# ST-Link_V2.net
KiCad netlist of a schematic drawn in Altium Designer
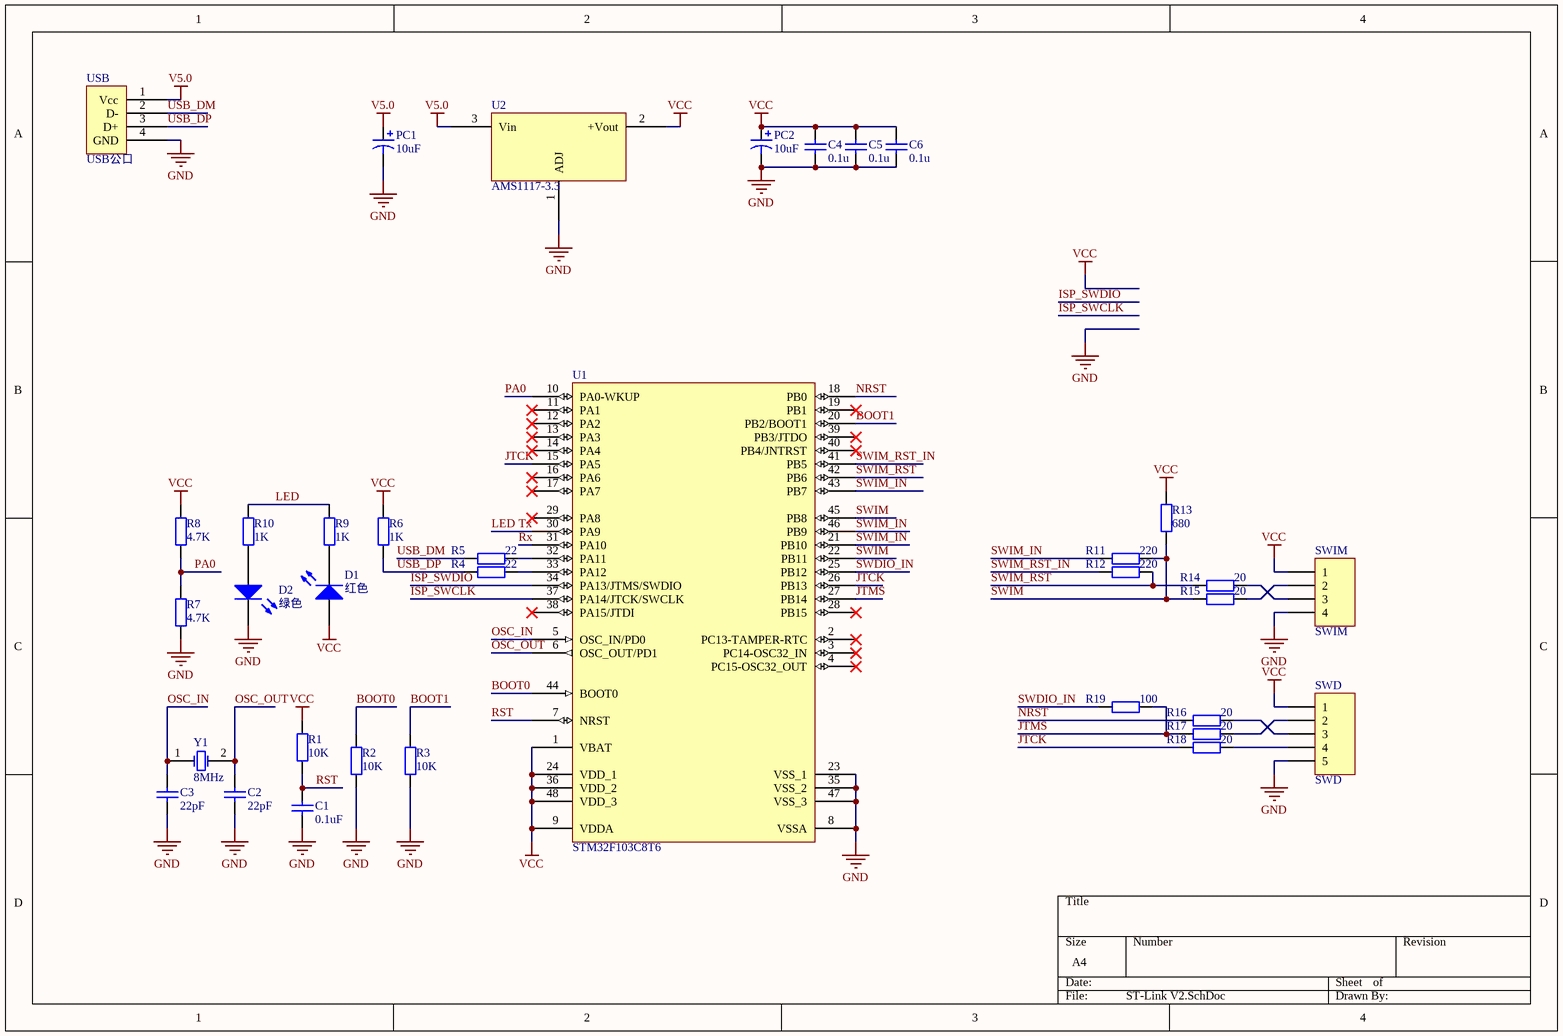
[diagram p0: ST-Link V2.SchDoc]

(export (version "E")
  (design (tool "Eeschema 10.0.6"))
  (components
    (comp (ref "C1")
      (value "0.1uF")
      (footprint "Teacher:C0603")
      (description "Capacitor")
      (fields (field (name "PUBLISHER") "Altium Limited"))
      (libsource (lib "Miscellaneous Devices") (part "Cap"))
    )
    (comp (ref "C2")
      (value "22pF")
      (footprint "Teacher:C0603")
      (description "Capacitor")
      (fields (field (name "PUBLISHER") "Altium Limited"))
      (libsource (lib "Miscellaneous Devices") (part "Cap"))
    )
    (comp (ref "C3")
      (value "22pF")
      (footprint "Teacher:C0603")
      (description "Capacitor")
      (fields (field (name "PUBLISHER") "Altium Limited"))
      (libsource (lib "Miscellaneous Devices") (part "Cap"))
    )
    (comp (ref "C4")
      (value "0.1u")
      (description "Capacitor")
      (fields (field (name "PUBLISHER") "Altium Limited"))
      (libsource (lib "Miscellaneous Devices") (part "Cap"))
    )
    (comp (ref "C5")
      (value "0.1u")
      (description "Capacitor")
      (fields (field (name "PUBLISHER") "Altium Limited"))
      (libsource (lib "Miscellaneous Devices") (part "Cap"))
    )
    (comp (ref "C6")
      (value "0.1u")
      (description "Capacitor")
      (fields (field (name "PUBLISHER") "Altium Limited"))
      (libsource (lib "Miscellaneous Devices") (part "Cap"))
    )
    (comp (ref "D1")
      (value "红色")
      (footprint "ADqun:LED0603")
      (description "Typical RED, GREEN, YELLOW, AMBER GaAs LED")
      (fields (field (name "PUBLISHER") "Altium Limited"))
      (libsource (lib "Miscellaneous Devices") (part "LED2"))
    )
    (comp (ref "D2")
      (value "绿色")
      (footprint "ADqun:LED0603")
      (description "Typical RED, GREEN, YELLOW, AMBER GaAs LED")
      (fields (field (name "PUBLISHER") "Altium Limited"))
      (libsource (lib "Miscellaneous Devices") (part "LED2"))
    )
    (comp (ref "PC1")
      (value "10uF")
      (footprint "Teacher:C1206A")
      (description "Polarized Capacitor (Surface Mount)")
      (fields (field (name "PUBLISHER") "Altium Limited"))
      (libsource (lib "Miscellaneous Devices") (part "Cap Pol3"))
    )
    (comp (ref "PC2")
      (value "10uF")
      (footprint "Teacher:C1206A")
      (description "Polarized Capacitor (Surface Mount)")
      (fields (field (name "PUBLISHER") "Altium Limited"))
      (libsource (lib "Miscellaneous Devices") (part "Cap Pol3"))
    )
    (comp (ref "R1")
      (value "10K")
      (footprint "Teacher:R0603")
      (description "Resistor")
      (fields (field (name "PUBLISHER") "Altium Limited"))
      (libsource (lib "") (part "Res2_2"))
    )
    (comp (ref "R2")
      (value "10K")
      (footprint "Teacher:R0603")
      (description "Resistor")
      (fields (field (name "PUBLISHER") "Altium Limited"))
      (libsource (lib "") (part "Res2_2"))
    )
    (comp (ref "R3")
      (value "10K")
      (footprint "Teacher:R0603")
      (description "Resistor")
      (fields (field (name "PUBLISHER") "Altium Limited"))
      (libsource (lib "") (part "Res2_2"))
    )
    (comp (ref "R4")
      (value "22")
      (footprint "Teacher:R0603")
      (description "Resistor")
      (fields (field (name "PUBLISHER") "Altium Limited"))
      (libsource (lib "") (part "Res2_1"))
    )
    (comp (ref "R5")
      (value "22")
      (footprint "Teacher:R0603")
      (description "Resistor")
      (fields (field (name "PUBLISHER") "Altium Limited"))
      (libsource (lib "") (part "Res2_1"))
    )
    (comp (ref "R6")
      (value "1K")
      (footprint "Teacher:R0603")
      (description "Resistor")
      (fields (field (name "PUBLISHER") "Altium Limited"))
      (libsource (lib "") (part "Res2_3"))
    )
    (comp (ref "R7")
      (value "4.7K")
      (footprint "Teacher:R0603")
      (description "Resistor")
      (fields (field (name "PUBLISHER") "Altium Limited"))
      (libsource (lib "") (part "Res2_3"))
    )
    (comp (ref "R8")
      (value "4.7K")
      (footprint "Teacher:R0603")
      (description "Resistor")
      (fields (field (name "PUBLISHER") "Altium Limited"))
      (libsource (lib "") (part "Res2_3"))
    )
    (comp (ref "R9")
      (value "1K")
      (footprint "Teacher:R0603")
      (description "Resistor")
      (fields (field (name "PUBLISHER") "Altium Limited"))
      (libsource (lib "") (part "Res2_3"))
    )
    (comp (ref "R10")
      (value "1K")
      (footprint "Teacher:R0603")
      (description "Resistor")
      (fields (field (name "PUBLISHER") "Altium Limited"))
      (libsource (lib "") (part "Res2_3"))
    )
    (comp (ref "R11")
      (value "220")
      (footprint "Teacher:R0603")
      (description "Resistor")
      (fields (field (name "PUBLISHER") "Altium Limited"))
      (libsource (lib "Miscellaneous Devices") (part "Res2"))
    )
    (comp (ref "R12")
      (value "220")
      (footprint "Teacher:R0603")
      (description "Resistor")
      (fields (field (name "PUBLISHER") "Altium Limited"))
      (libsource (lib "Miscellaneous Devices") (part "Res2"))
    )
    (comp (ref "R13")
      (value "680")
      (footprint "Teacher:R0603")
      (description "Resistor")
      (fields (field (name "PUBLISHER") "Altium Limited"))
      (libsource (lib "") (part "Res2_2"))
    )
    (comp (ref "R14")
      (value "20")
      (footprint "Teacher:R0603")
      (description "Resistor")
      (fields (field (name "PUBLISHER") "Altium Limited"))
      (libsource (lib "") (part "Res2_1"))
    )
    (comp (ref "R15")
      (value "20")
      (footprint "Teacher:R0603")
      (description "Resistor")
      (fields (field (name "PUBLISHER") "Altium Limited"))
      (libsource (lib "") (part "Res2_1"))
    )
    (comp (ref "R16")
      (value "20")
      (footprint "Teacher:R0603")
      (description "Resistor")
      (fields (field (name "PUBLISHER") "Altium Limited"))
      (libsource (lib "") (part "Res2_1"))
    )
    (comp (ref "R17")
      (value "20")
      (footprint "Teacher:R0603")
      (description "Resistor")
      (fields (field (name "PUBLISHER") "Altium Limited"))
      (libsource (lib "") (part "Res2_1"))
    )
    (comp (ref "R18")
      (value "20")
      (footprint "Teacher:R0603")
      (description "Resistor")
      (fields (field (name "PUBLISHER") "Altium Limited"))
      (libsource (lib "") (part "Res2_1"))
    )
    (comp (ref "R19")
      (value "100")
      (footprint "Teacher:R0603")
      (description "Resistor")
      (fields (field (name "PUBLISHER") "Altium Limited"))
      (libsource (lib "") (part "Res2_1"))
    )
    (comp (ref "SWD")
      (value "SWD")
      (footprint "HDR1X5")
      (description "Header, 5-Pin")
      (fields (field (name "PUBLISHER") "Altium Limited"))
      (libsource (lib "Miscellaneous Connectors") (part "Header 5"))
    )
    (comp (ref "SWIM")
      (value "SWIM")
      (footprint "HDR1X4")
      (description "Header, 4-Pin")
      (fields (field (name "PUBLISHER") "Altium Limited"))
      (libsource (lib "Miscellaneous Connectors") (part "Header 4"))
    )
    (comp (ref "U1")
      (value "STM32F103C8T6")
      (footprint "LQFP48_M")
      (description "STM32 ARM-based 32-bit MCU with 64 Kbytes Flash, 48-pin LQFP, Industrial Temperature")
      (fields (field (name "PUBLISHER") "Altium Limited"))
      (libsource (lib "ST Microcontroller 32-Bit STM32") (part "STM32F103C8T6"))
    )
    (comp (ref "U2")
      (value "AMS1117-3.3")
      (footprint "Teacher:SOT-223")
      (libsource (lib "Protel DOS Schematic Libraries") (part "LM117T"))
    )
    (comp (ref "USB") (value "USB公口") (footprint "USB-H") (libsource (lib "USB公口") (part "USB公口")))
    (comp (ref "Y1")
      (value "8MHz")
      (footprint "paul_pcb:JZ")
      (description "Crystal Oscillator")
      (fields (field (name "PUBLISHER") "Altium Limited"))
      (libsource (lib "Miscellaneous Devices") (part "XTAL"))
    )
  )
  (nets
    (net (code "1") (name "/BOOT0") (class "Default")
      (node (ref "R2") (pin "2") (pinfunction "2_2") (pintype "passive"))
      (node (ref "U1") (pin "44") (pinfunction "BOOT0_44") (pintype "input"))
    )
    (net (code "2") (name "/BOOT1") (class "Default")
      (node (ref "R3") (pin "2") (pinfunction "2_2") (pintype "passive"))
      (node (ref "U1") (pin "20") (pinfunction "PB2/BOOT1_20") (pintype "bidirectional"))
    )
    (net (code "3") (name "/ISP_SWCLK") (class "Default")
      (node (ref "U1") (pin "37") (pinfunction "PA14/JTCK/SWCLK_37") (pintype "bidirectional"))
    )
    (net (code "4") (name "/ISP_SWDIO") (class "Default")
      (node (ref "U1") (pin "34") (pinfunction "PA13/JTMS/SWDIO_34") (pintype "bidirectional"))
    )
    (net (code "5") (name "/JTCK") (class "Default")
      (node (ref "R18") (pin "2") (pinfunction "2_2") (pintype "passive"))
      (node (ref "U1") (pin "15") (pinfunction "PA5_15") (pintype "bidirectional"))
      (node (ref "U1") (pin "26") (pinfunction "PB13_26") (pintype "bidirectional"))
    )
    (net (code "6") (name "/JTMS") (class "Default")
      (node (ref "R17") (pin "2") (pinfunction "2_2") (pintype "passive"))
      (node (ref "R19") (pin "1") (pinfunction "1_1") (pintype "passive"))
      (node (ref "U1") (pin "27") (pinfunction "PB14_27") (pintype "bidirectional"))
    )
    (net (code "7") (name "/LED") (class "Default")
      (node (ref "R10") (pin "1") (pinfunction "1_1") (pintype "passive"))
      (node (ref "R9") (pin "1") (pinfunction "1_1") (pintype "passive"))
      (node (ref "U1") (pin "30") (pinfunction "PA9_30") (pintype "bidirectional"))
    )
    (net (code "8") (name "/NRST") (class "Default")
      (node (ref "R16") (pin "2") (pinfunction "2_2") (pintype "passive"))
      (node (ref "U1") (pin "18") (pinfunction "PB0_18") (pintype "bidirectional"))
    )
    (net (code "9") (name "/OSC_IN") (class "Default")
      (node (ref "C3") (pin "1") (pinfunction "1_1") (pintype "passive"))
      (node (ref "U1") (pin "5") (pinfunction "OSC_IN/PD0_5") (pintype "input"))
      (node (ref "Y1") (pin "1") (pinfunction "OSC1_1") (pintype "passive"))
    )
    (net (code "10") (name "/OSC_OUT") (class "Default")
      (node (ref "C2") (pin "1") (pinfunction "1_1") (pintype "passive"))
      (node (ref "U1") (pin "6") (pinfunction "OSC_OUT/PD1_6") (pintype "output"))
      (node (ref "Y1") (pin "2") (pinfunction "OSC2_2") (pintype "passive"))
    )
    (net (code "11") (name "/PA0") (class "Default")
      (node (ref "R7") (pin "1") (pinfunction "1_1") (pintype "passive"))
      (node (ref "R8") (pin "2") (pinfunction "2_2") (pintype "passive"))
      (node (ref "U1") (pin "10") (pinfunction "PA0-WKUP_10") (pintype "bidirectional"))
    )
    (net (code "12") (name "/RST") (class "Default")
      (node (ref "C1") (pin "1") (pinfunction "1_1") (pintype "passive"))
      (node (ref "R1") (pin "1") (pinfunction "1_1") (pintype "passive"))
      (node (ref "U1") (pin "7") (pinfunction "NRST_7") (pintype "bidirectional"))
    )
    (net (code "13") (name "/Rx") (class "Default")
      (node (ref "U1") (pin "31") (pinfunction "PA10_31") (pintype "bidirectional"))
    )
    (net (code "14") (name "/SWDIO_IN") (class "Default")
      (node (ref "R19") (pin "2") (pinfunction "2_2") (pintype "passive"))
      (node (ref "U1") (pin "25") (pinfunction "PB12_25") (pintype "bidirectional"))
    )
    (net (code "15") (name "/SWIM") (class "Default")
      (node (ref "R11") (pin "2") (pinfunction "2_2") (pintype "passive"))
      (node (ref "R13") (pin "1") (pinfunction "1_1") (pintype "passive"))
      (node (ref "R15") (pin "2") (pinfunction "2_2") (pintype "passive"))
      (node (ref "U1") (pin "22") (pinfunction "PB11_22") (pintype "bidirectional"))
      (node (ref "U1") (pin "45") (pinfunction "PB8_45") (pintype "bidirectional"))
    )
    (net (code "16") (name "/SWIM_IN") (class "Default")
      (node (ref "R11") (pin "1") (pinfunction "1_1") (pintype "passive"))
      (node (ref "U1") (pin "21") (pinfunction "PB10_21") (pintype "bidirectional"))
      (node (ref "U1") (pin "43") (pinfunction "PB7_43") (pintype "bidirectional"))
      (node (ref "U1") (pin "46") (pinfunction "PB9_46") (pintype "bidirectional"))
    )
    (net (code "17") (name "/SWIM_RST") (class "Default")
      (node (ref "R12") (pin "2") (pinfunction "2_2") (pintype "passive"))
      (node (ref "R14") (pin "2") (pinfunction "2_2") (pintype "passive"))
      (node (ref "U1") (pin "42") (pinfunction "PB6_42") (pintype "bidirectional"))
    )
    (net (code "18") (name "/SWIM_RST_IN") (class "Default")
      (node (ref "R12") (pin "1") (pinfunction "1_1") (pintype "passive"))
      (node (ref "U1") (pin "41") (pinfunction "PB5_41") (pintype "bidirectional"))
    )
    (net (code "19") (name "/USB_DM") (class "Default")
      (node (ref "R5") (pin "2") (pinfunction "2_2") (pintype "passive"))
      (node (ref "USB") (pin "2") (pinfunction "D-_2") (pintype "passive"))
    )
    (net (code "20") (name "/USB_DP") (class "Default")
      (node (ref "R4") (pin "2") (pinfunction "2_2") (pintype "passive"))
      (node (ref "R6") (pin "2") (pinfunction "2_2") (pintype "passive"))
      (node (ref "USB") (pin "3") (pinfunction "D+_3") (pintype "passive"))
    )
    (net (code "21") (name "GND") (class "Default")
      (node (ref "C1") (pin "2") (pinfunction "2_2") (pintype "passive"))
      (node (ref "C2") (pin "2") (pinfunction "2_2") (pintype "passive"))
      (node (ref "C3") (pin "2") (pinfunction "2_2") (pintype "passive"))
      (node (ref "C4") (pin "2") (pinfunction "2_2") (pintype "passive"))
      (node (ref "C5") (pin "2") (pinfunction "2_2") (pintype "passive"))
      (node (ref "C6") (pin "2") (pinfunction "2_2") (pintype "passive"))
      (node (ref "D2") (pin "2") (pinfunction "K_2") (pintype "passive"))
      (node (ref "PC1") (pin "2") (pinfunction "2_2") (pintype "passive"))
      (node (ref "PC2") (pin "2") (pinfunction "2_2") (pintype "passive"))
      (node (ref "R2") (pin "1") (pinfunction "1_1") (pintype "passive"))
      (node (ref "R3") (pin "1") (pinfunction "1_1") (pintype "passive"))
      (node (ref "R7") (pin "2") (pinfunction "2_2") (pintype "passive"))
      (node (ref "SWD") (pin "5") (pinfunction "5_5") (pintype "passive"))
      (node (ref "SWIM") (pin "4") (pinfunction "4_4") (pintype "passive"))
      (node (ref "U1") (pin "23") (pinfunction "VSS_1_23") (pintype "power_in"))
      (node (ref "U1") (pin "35") (pinfunction "VSS_2_35") (pintype "power_in"))
      (node (ref "U1") (pin "47") (pinfunction "VSS_3_47") (pintype "power_in"))
      (node (ref "U1") (pin "8") (pinfunction "VSSA_8") (pintype "power_in"))
      (node (ref "U2") (pin "1") (pinfunction "ADJ_1") (pintype "passive"))
      (node (ref "USB") (pin "4") (pinfunction "GND_4") (pintype "passive"))
    )
    (net (code "22") (name "Net-(D1-K)") (class "Default")
      (node (ref "D1") (pin "2") (pinfunction "K_2") (pintype "passive"))
      (node (ref "R9") (pin "2") (pinfunction "2_2") (pintype "passive"))
    )
    (net (code "23") (name "Net-(D2-A)") (class "Default")
      (node (ref "D2") (pin "1") (pinfunction "A_1") (pintype "passive"))
      (node (ref "R10") (pin "2") (pinfunction "2_2") (pintype "passive"))
    )
    (net (code "24") (name "Net-(R14-Pad1)") (class "Default")
      (node (ref "R14") (pin "1") (pinfunction "1_1") (pintype "passive"))
      (node (ref "SWIM") (pin "3") (pinfunction "3_3") (pintype "passive"))
    )
    (net (code "25") (name "Net-(R15-Pad1)") (class "Default")
      (node (ref "R15") (pin "1") (pinfunction "1_1") (pintype "passive"))
      (node (ref "SWIM") (pin "2") (pinfunction "2_2") (pintype "passive"))
    )
    (net (code "26") (name "Net-(R16-Pad1)") (class "Default")
      (node (ref "R16") (pin "1") (pinfunction "1_1") (pintype "passive"))
      (node (ref "SWD") (pin "3") (pinfunction "3_3") (pintype "passive"))
    )
    (net (code "27") (name "Net-(R17-Pad1)") (class "Default")
      (node (ref "R17") (pin "1") (pinfunction "1_1") (pintype "passive"))
      (node (ref "SWD") (pin "2") (pinfunction "2_2") (pintype "passive"))
    )
    (net (code "28") (name "Net-(R18-Pad1)") (class "Default")
      (node (ref "R18") (pin "1") (pinfunction "1_1") (pintype "passive"))
      (node (ref "SWD") (pin "4") (pinfunction "4_4") (pintype "passive"))
    )
    (net (code "29") (name "Net-(U1-PA11)") (class "Default")
      (node (ref "R5") (pin "1") (pinfunction "1_1") (pintype "passive"))
      (node (ref "U1") (pin "32") (pinfunction "PA11_32") (pintype "bidirectional"))
    )
    (net (code "30") (name "Net-(U1-PA12)") (class "Default")
      (node (ref "R4") (pin "1") (pinfunction "1_1") (pintype "passive"))
      (node (ref "U1") (pin "33") (pinfunction "PA12_33") (pintype "bidirectional"))
    )
    (net (code "31") (name "V5.0") (class "Default")
      (node (ref "PC1") (pin "1") (pinfunction "1_1") (pintype "passive"))
      (node (ref "U2") (pin "3") (pinfunction "Vin_3") (pintype "passive"))
      (node (ref "USB") (pin "1") (pinfunction "Vcc_1") (pintype "passive"))
    )
    (net (code "32") (name "VCC") (class "Default")
      (node (ref "C4") (pin "1") (pinfunction "1_1") (pintype "passive"))
      (node (ref "C5") (pin "1") (pinfunction "1_1") (pintype "passive"))
      (node (ref "C6") (pin "1") (pinfunction "1_1") (pintype "passive"))
      (node (ref "D1") (pin "1") (pinfunction "A_1") (pintype "passive"))
      (node (ref "PC2") (pin "1") (pinfunction "1_1") (pintype "passive"))
      (node (ref "R1") (pin "2") (pinfunction "2_2") (pintype "passive"))
      (node (ref "R13") (pin "2") (pinfunction "2_2") (pintype "passive"))
      (node (ref "R6") (pin "1") (pinfunction "1_1") (pintype "passive"))
      (node (ref "R8") (pin "1") (pinfunction "1_1") (pintype "passive"))
      (node (ref "SWD") (pin "1") (pinfunction "1_1") (pintype "passive"))
      (node (ref "SWIM") (pin "1") (pinfunction "1_1") (pintype "passive"))
      (node (ref "U1") (pin "1") (pinfunction "VBAT_1") (pintype "power_in"))
      (node (ref "U1") (pin "24") (pinfunction "VDD_1_24") (pintype "power_in"))
      (node (ref "U1") (pin "36") (pinfunction "VDD_2_36") (pintype "power_in"))
      (node (ref "U1") (pin "48") (pinfunction "VDD_3_48") (pintype "power_in"))
      (node (ref "U1") (pin "9") (pinfunction "VDDA_9") (pintype "power_in"))
      (node (ref "U2") (pin "2") (pinfunction "+Vout_2") (pintype "passive"))
    )
    (net (code "33") (name "unconnected-(U1-PA1-Pad11)") (class "Default")
      (node (ref "U1") (pin "11") (pinfunction "PA1_11") (pintype "bidirectional+no_connect"))
    )
    (net (code "34") (name "unconnected-(U1-PA2-Pad12)") (class "Default")
      (node (ref "U1") (pin "12") (pinfunction "PA2_12") (pintype "bidirectional+no_connect"))
    )
    (net (code "35") (name "unconnected-(U1-PA3-Pad13)") (class "Default")
      (node (ref "U1") (pin "13") (pinfunction "PA3_13") (pintype "bidirectional+no_connect"))
    )
    (net (code "36") (name "unconnected-(U1-PA4-Pad14)") (class "Default")
      (node (ref "U1") (pin "14") (pinfunction "PA4_14") (pintype "bidirectional+no_connect"))
    )
    (net (code "37") (name "unconnected-(U1-PA6-Pad16)") (class "Default")
      (node (ref "U1") (pin "16") (pinfunction "PA6_16") (pintype "bidirectional+no_connect"))
    )
    (net (code "38") (name "unconnected-(U1-PA7-Pad17)") (class "Default")
      (node (ref "U1") (pin "17") (pinfunction "PA7_17") (pintype "bidirectional+no_connect"))
    )
    (net (code "39") (name "unconnected-(U1-PA8-Pad29)") (class "Default")
      (node (ref "U1") (pin "29") (pinfunction "PA8_29") (pintype "bidirectional+no_connect"))
    )
    (net (code "40") (name "unconnected-(U1-PA15{slash}JTDI-Pad38)") (class "Default")
      (node (ref "U1") (pin "38") (pinfunction "PA15/JTDI_38") (pintype "bidirectional+no_connect"))
    )
    (net (code "41") (name "unconnected-(U1-PB1-Pad19)") (class "Default")
      (node (ref "U1") (pin "19") (pinfunction "PB1_19") (pintype "bidirectional+no_connect"))
    )
    (net (code "42") (name "unconnected-(U1-PB3{slash}JTDO-Pad39)") (class "Default")
      (node (ref "U1") (pin "39") (pinfunction "PB3/JTDO_39") (pintype "bidirectional+no_connect"))
    )
    (net (code "43") (name "unconnected-(U1-PB4{slash}JNTRST-Pad40)") (class "Default")
      (node (ref "U1") (pin "40") (pinfunction "PB4/JNTRST_40") (pintype "bidirectional+no_connect"))
    )
    (net (code "44") (name "unconnected-(U1-PB15-Pad28)") (class "Default")
      (node (ref "U1") (pin "28") (pinfunction "PB15_28") (pintype "bidirectional+no_connect"))
    )
    (net (code "45") (name "unconnected-(U1-PC13-TAMPER-RTC-Pad2)") (class "Default")
      (node (ref "U1") (pin "2") (pinfunction "PC13-TAMPER-RTC_2") (pintype "bidirectional+no_connect"))
    )
    (net (code "46") (name "unconnected-(U1-PC14-OSC32_IN-Pad3)") (class "Default")
      (node (ref "U1") (pin "3") (pinfunction "PC14-OSC32_IN_3") (pintype "bidirectional+no_connect"))
    )
    (net (code "47") (name "unconnected-(U1-PC15-OSC32_OUT-Pad4)") (class "Default")
      (node (ref "U1") (pin "4") (pinfunction "PC15-OSC32_OUT_4") (pintype "bidirectional+no_connect"))
    )
  )
)
